# SCH_Senior_Transmitter_2026-04-06.net
KiCad netlist of a schematic drawn in EasyEDA
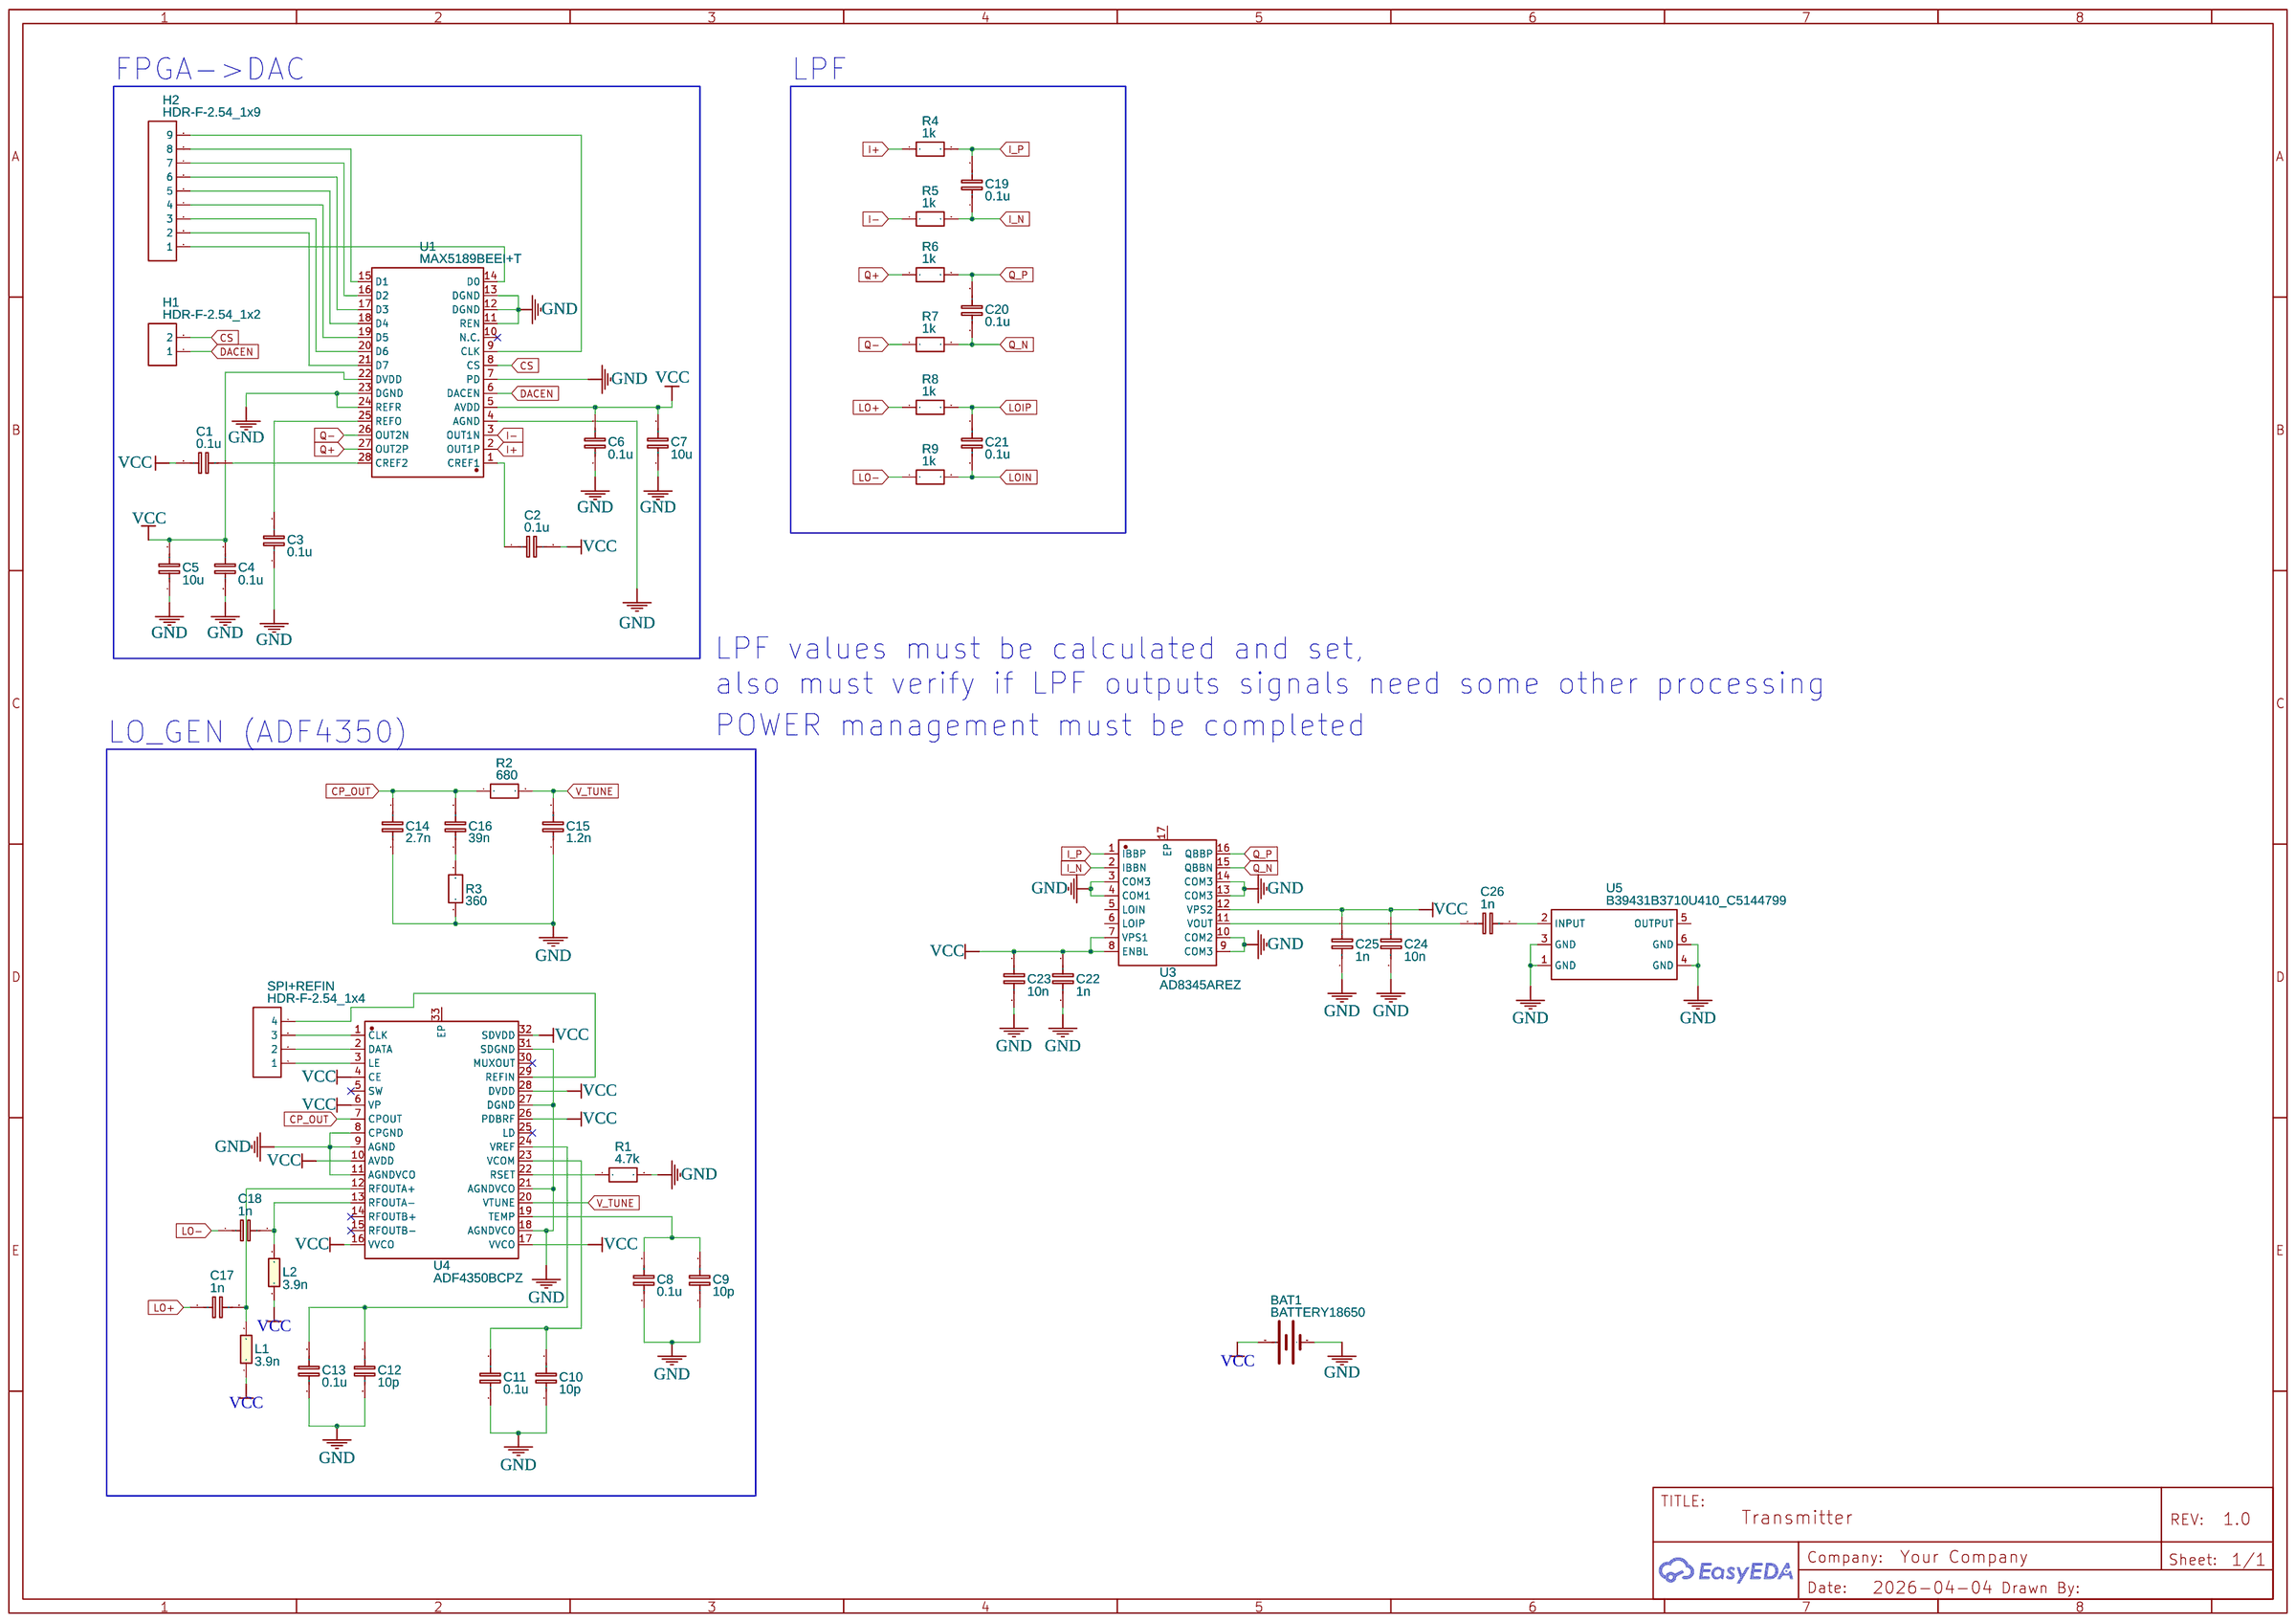
[diagram p0: schematic sheet]

(export (version "E")
  (design (tool "Eeschema 10.0.6"))
  (components
    (comp (ref "BAT1") (value "BATTERY18650") (libsource (lib "") (part "BATTERY18650")))
    (comp (ref "C1") (value "0.1u") (libsource (lib "") (part "C_0603_EU_3")))
    (comp (ref "C2") (value "0.1u") (libsource (lib "") (part "C_0603_EU_3")))
    (comp (ref "C3") (value "0.1u") (libsource (lib "") (part "C_0603_EU_1")))
    (comp (ref "C4") (value "0.1u") (libsource (lib "") (part "C_0603_EU_1")))
    (comp (ref "C5") (value "10u") (libsource (lib "") (part "C_0603_EU_1")))
    (comp (ref "C6") (value "0.1u") (libsource (lib "") (part "C_0603_EU_4")))
    (comp (ref "C7") (value "10u") (libsource (lib "") (part "C_0603_EU_4")))
    (comp (ref "C8") (value "0.1u") (libsource (lib "") (part "C_0603_EU_5")))
    (comp (ref "C9") (value "10p") (libsource (lib "") (part "C_0603_EU_5")))
    (comp (ref "C10") (value "10p") (libsource (lib "") (part "C_0603_EU_4")))
    (comp (ref "C11") (value "0.1u") (libsource (lib "") (part "C_0603_EU_4")))
    (comp (ref "C12") (value "10p") (libsource (lib "") (part "C_0603_EU_4")))
    (comp (ref "C13") (value "0.1u") (libsource (lib "") (part "C_0603_EU_1")))
    (comp (ref "C14") (value "2.7n") (libsource (lib "") (part "C_0603_EU_5")))
    (comp (ref "C15") (value "1.2n") (libsource (lib "") (part "C_0603_EU_5")))
    (comp (ref "C16") (value "39n") (libsource (lib "") (part "C_0603_EU_5")))
    (comp (ref "C17") (value "1n") (libsource (lib "") (part "C_0603_EU_3")))
    (comp (ref "C18") (value "1n") (libsource (lib "") (part "C_0603_EU_6")))
    (comp (ref "C19") (value "0.1u") (libsource (lib "") (part "C_0603_EU_1")))
    (comp (ref "C20") (value "0.1u") (libsource (lib "") (part "C_0603_EU_1")))
    (comp (ref "C21") (value "0.1u") (libsource (lib "") (part "C_0603_EU_1")))
    (comp (ref "C22") (value "1n") (libsource (lib "") (part "C_0603_EU")))
    (comp (ref "C23") (value "10n") (libsource (lib "") (part "C_0603_EU")))
    (comp (ref "C24") (value "10n") (libsource (lib "") (part "C_0603_EU")))
    (comp (ref "C25") (value "1n") (libsource (lib "") (part "C_0603_EU")))
    (comp (ref "C26") (value "1n") (libsource (lib "") (part "C_0603_EU_2")))
    (comp (ref "H1") (value "HDR-F-2.54_1x2") (libsource (lib "") (part "HDR-F-2.54_1x2")))
    (comp (ref "H2") (value "HDR-F-2.54_1x9") (libsource (lib "") (part "HDR-F-2.54_1x9")))
    (comp (ref "L1") (value "3.9n") (libsource (lib "") (part "L0603_EU")))
    (comp (ref "L2") (value "3.9n") (libsource (lib "") (part "L0603_EU")))
    (comp (ref "R1") (value "4.7k") (libsource (lib "") (part "R_0603_EU")))
    (comp (ref "R2") (value "680") (libsource (lib "") (part "R_0603_EU")))
    (comp (ref "R3") (value "360") (libsource (lib "") (part "R_0603_EU_1")))
    (comp (ref "R4") (value "1k") (libsource (lib "") (part "R_0603_EU")))
    (comp (ref "R5") (value "1k") (libsource (lib "") (part "R_0603_EU")))
    (comp (ref "R6") (value "1k") (libsource (lib "") (part "R_0603_EU")))
    (comp (ref "R7") (value "1k") (libsource (lib "") (part "R_0603_EU")))
    (comp (ref "R8") (value "1k") (libsource (lib "") (part "R_0603_EU")))
    (comp (ref "R9") (value "1k") (libsource (lib "") (part "R_0603_EU")))
    (comp (ref "SPI+REFIN") (value "HDR-F-2.54_1x4") (libsource (lib "") (part "HDR-F-2.54_1x4")))
    (comp (ref "U1")
      (value "MAX5189BEEI+T")
      (fields (field (name "Manufacturer") "ADI(亚德诺)/MAXIM(美信)"))
      (libsource (lib "") (part "MAX5189BEEI+T"))
    )
    (comp (ref "U3")
      (value "AD8345AREZ")
      (fields (field (name "Manufacturer") "ADI(亚德诺)"))
      (libsource (lib "") (part "AD8345AREZ"))
    )
    (comp (ref "U4")
      (value "ADF4350BCPZ")
      (fields (field (name "Manufacturer") "ADI(亚德诺)"))
      (libsource (lib "") (part "ADF4350BCPZ"))
    )
    (comp (ref "U5")
      (value "B39431B3710U410_C5144799")
      (fields (field (name "Manufacturer Part") "B39431B3710U410"))
      (libsource (lib "") (part "B39431B3710U410_C5144799"))
    )
  )
  (nets
    (net (code "1") (name "CP_OUT") (class "Default")
      (node (ref "C14") (pin "2") (pinfunction "2_2") (pintype "unspecified"))
      (node (ref "C16") (pin "2") (pinfunction "2_2") (pintype "unspecified"))
      (node (ref "R2") (pin "1") (pinfunction "1_1") (pintype "unspecified"))
      (node (ref "U4") (pin "7") (pinfunction "CPOUT_7") (pintype "unspecified"))
    )
    (net (code "2") (name "CS") (class "Default")
      (node (ref "H1") (pin "2") (pinfunction "2_2") (pintype "input"))
      (node (ref "U1") (pin "8") (pinfunction "CS_8") (pintype "unspecified"))
    )
    (net (code "3") (name "DACEN") (class "Default")
      (node (ref "H1") (pin "1") (pinfunction "1_1") (pintype "input"))
      (node (ref "U1") (pin "6") (pinfunction "DACEN_6") (pintype "unspecified"))
    )
    (net (code "4") (name "GND") (class "Default")
      (node (ref "BAT1") (pin "GND@1") (pinfunction "-_GND@1") (pintype "passive"))
      (node (ref "C10") (pin "1") (pinfunction "1_1") (pintype "unspecified"))
      (node (ref "C11") (pin "1") (pinfunction "1_1") (pintype "unspecified"))
      (node (ref "C12") (pin "1") (pinfunction "1_1") (pintype "unspecified"))
      (node (ref "C13") (pin "1") (pinfunction "1_1") (pintype "unspecified"))
      (node (ref "C14") (pin "1") (pinfunction "1_1") (pintype "unspecified"))
      (node (ref "C15") (pin "1") (pinfunction "1_1") (pintype "unspecified"))
      (node (ref "C22") (pin "2") (pinfunction "2_2") (pintype "unspecified"))
      (node (ref "C23") (pin "2") (pinfunction "2_2") (pintype "unspecified"))
      (node (ref "C24") (pin "2") (pinfunction "2_2") (pintype "unspecified"))
      (node (ref "C25") (pin "2") (pinfunction "2_2") (pintype "unspecified"))
      (node (ref "C3") (pin "1") (pinfunction "1_1") (pintype "unspecified"))
      (node (ref "C4") (pin "1") (pinfunction "1_1") (pintype "unspecified"))
      (node (ref "C5") (pin "1") (pinfunction "1_1") (pintype "unspecified"))
      (node (ref "C6") (pin "1") (pinfunction "1_1") (pintype "unspecified"))
      (node (ref "C7") (pin "1") (pinfunction "1_1") (pintype "unspecified"))
      (node (ref "C8") (pin "1") (pinfunction "1_1") (pintype "unspecified"))
      (node (ref "C9") (pin "1") (pinfunction "1_1") (pintype "unspecified"))
      (node (ref "R1") (pin "2") (pinfunction "2_2") (pintype "unspecified"))
      (node (ref "R3") (pin "1") (pinfunction "1_1") (pintype "unspecified"))
      (node (ref "U1") (pin "11") (pinfunction "REN_11") (pintype "unspecified"))
      (node (ref "U1") (pin "12") (pinfunction "DGND_12") (pintype "unspecified"))
      (node (ref "U1") (pin "13") (pinfunction "DGND_13") (pintype "unspecified"))
      (node (ref "U1") (pin "23") (pinfunction "DGND_23") (pintype "unspecified"))
      (node (ref "U1") (pin "24") (pinfunction "REFR_24") (pintype "unspecified"))
      (node (ref "U1") (pin "4") (pinfunction "AGND_4") (pintype "unspecified"))
      (node (ref "U1") (pin "7") (pinfunction "PD_7") (pintype "unspecified"))
      (node (ref "U3") (pin "10") (pinfunction "COM2_10") (pintype "unspecified"))
      (node (ref "U3") (pin "13") (pinfunction "COM3_13") (pintype "unspecified"))
      (node (ref "U3") (pin "14") (pinfunction "COM3_14") (pintype "unspecified"))
      (node (ref "U3") (pin "3") (pinfunction "COM3_3") (pintype "unspecified"))
      (node (ref "U3") (pin "4") (pinfunction "COM1_4") (pintype "unspecified"))
      (node (ref "U3") (pin "9") (pinfunction "COM3_9") (pintype "unspecified"))
      (node (ref "U4") (pin "11") (pinfunction "AGNDVCO_11") (pintype "unspecified"))
      (node (ref "U4") (pin "18") (pinfunction "AGNDVCO_18") (pintype "unspecified"))
      (node (ref "U4") (pin "21") (pinfunction "AGNDVCO_21") (pintype "unspecified"))
      (node (ref "U4") (pin "27") (pinfunction "DGND_27") (pintype "unspecified"))
      (node (ref "U4") (pin "31") (pinfunction "SDGND_31") (pintype "unspecified"))
      (node (ref "U4") (pin "8") (pinfunction "CPGND_8") (pintype "unspecified"))
      (node (ref "U4") (pin "9") (pinfunction "AGND_9") (pintype "unspecified"))
      (node (ref "U5") (pin "1") (pinfunction "GND_1") (pintype "unspecified"))
      (node (ref "U5") (pin "3") (pinfunction "GND_3") (pintype "unspecified"))
      (node (ref "U5") (pin "4") (pinfunction "GND_4") (pintype "unspecified"))
      (node (ref "U5") (pin "6") (pinfunction "GND_6") (pintype "unspecified"))
    )
    (net (code "5") (name "I+") (class "Default")
      (node (ref "R4") (pin "1") (pinfunction "1_1") (pintype "unspecified"))
      (node (ref "U1") (pin "2") (pinfunction "OUT1P_2") (pintype "unspecified"))
    )
    (net (code "6") (name "I-") (class "Default")
      (node (ref "R5") (pin "1") (pinfunction "1_1") (pintype "unspecified"))
      (node (ref "U1") (pin "3") (pinfunction "OUT1N_3") (pintype "unspecified"))
    )
    (net (code "7") (name "I_N") (class "Default")
      (node (ref "C19") (pin "1") (pinfunction "1_1") (pintype "unspecified"))
      (node (ref "R5") (pin "2") (pinfunction "2_2") (pintype "unspecified"))
      (node (ref "U3") (pin "2") (pinfunction "IBBN_2") (pintype "unspecified"))
    )
    (net (code "8") (name "I_P") (class "Default")
      (node (ref "C19") (pin "2") (pinfunction "2_2") (pintype "unspecified"))
      (node (ref "R4") (pin "2") (pinfunction "2_2") (pintype "unspecified"))
      (node (ref "U3") (pin "1") (pinfunction "IBBP_1") (pintype "unspecified"))
    )
    (net (code "9") (name "LO+") (class "Default")
      (node (ref "C17") (pin "1") (pinfunction "1_1") (pintype "unspecified"))
      (node (ref "R8") (pin "1") (pinfunction "1_1") (pintype "unspecified"))
    )
    (net (code "10") (name "LO-") (class "Default")
      (node (ref "C18") (pin "1") (pinfunction "1_1") (pintype "unspecified"))
      (node (ref "R9") (pin "1") (pinfunction "1_1") (pintype "unspecified"))
    )
    (net (code "11") (name "LOIN") (class "Default")
      (node (ref "C21") (pin "1") (pinfunction "1_1") (pintype "unspecified"))
      (node (ref "R9") (pin "2") (pinfunction "2_2") (pintype "unspecified"))
    )
    (net (code "12") (name "LOIP") (class "Default")
      (node (ref "C21") (pin "2") (pinfunction "2_2") (pintype "unspecified"))
      (node (ref "R8") (pin "2") (pinfunction "2_2") (pintype "unspecified"))
    )
    (net (code "13") (name "Net-(C16-Pad1)") (class "Default")
      (node (ref "C16") (pin "1") (pinfunction "1_1") (pintype "unspecified"))
      (node (ref "R3") (pin "2") (pinfunction "2_2") (pintype "unspecified"))
    )
    (net (code "14") (name "Net-(U1-CLK)") (class "Default")
      (node (ref "H2") (pin "9") (pinfunction "9_9") (pintype "unspecified"))
      (node (ref "U1") (pin "9") (pinfunction "CLK_9") (pintype "unspecified"))
    )
    (net (code "15") (name "Net-(U1-CREF1)") (class "Default")
      (node (ref "C2") (pin "1") (pinfunction "1_1") (pintype "unspecified"))
      (node (ref "U1") (pin "1") (pinfunction "CREF1_1") (pintype "unspecified"))
    )
    (net (code "16") (name "Net-(U1-CREF2)") (class "Default")
      (node (ref "C1") (pin "2") (pinfunction "2_2") (pintype "unspecified"))
      (node (ref "U1") (pin "28") (pinfunction "CREF2_28") (pintype "unspecified"))
    )
    (net (code "17") (name "Net-(U1-D0)") (class "Default")
      (node (ref "H2") (pin "1") (pinfunction "1_1") (pintype "unspecified"))
      (node (ref "U1") (pin "14") (pinfunction "D0_14") (pintype "unspecified"))
    )
    (net (code "18") (name "Net-(U1-D1)") (class "Default")
      (node (ref "H2") (pin "8") (pinfunction "8_8") (pintype "unspecified"))
      (node (ref "U1") (pin "15") (pinfunction "D1_15") (pintype "unspecified"))
    )
    (net (code "19") (name "Net-(U1-D2)") (class "Default")
      (node (ref "H2") (pin "7") (pinfunction "7_7") (pintype "unspecified"))
      (node (ref "U1") (pin "16") (pinfunction "D2_16") (pintype "unspecified"))
    )
    (net (code "20") (name "Net-(U1-D3)") (class "Default")
      (node (ref "H2") (pin "6") (pinfunction "6_6") (pintype "unspecified"))
      (node (ref "U1") (pin "17") (pinfunction "D3_17") (pintype "unspecified"))
    )
    (net (code "21") (name "Net-(U1-D4)") (class "Default")
      (node (ref "H2") (pin "5") (pinfunction "5_5") (pintype "unspecified"))
      (node (ref "U1") (pin "18") (pinfunction "D4_18") (pintype "unspecified"))
    )
    (net (code "22") (name "Net-(U1-D5)") (class "Default")
      (node (ref "H2") (pin "4") (pinfunction "4_4") (pintype "unspecified"))
      (node (ref "U1") (pin "19") (pinfunction "D5_19") (pintype "unspecified"))
    )
    (net (code "23") (name "Net-(U1-D6)") (class "Default")
      (node (ref "H2") (pin "3") (pinfunction "3_3") (pintype "unspecified"))
      (node (ref "U1") (pin "20") (pinfunction "D6_20") (pintype "unspecified"))
    )
    (net (code "24") (name "Net-(U1-D7)") (class "Default")
      (node (ref "H2") (pin "2") (pinfunction "2_2") (pintype "unspecified"))
      (node (ref "U1") (pin "21") (pinfunction "D7_21") (pintype "unspecified"))
    )
    (net (code "25") (name "Net-(U1-REFO)") (class "Default")
      (node (ref "C3") (pin "2") (pinfunction "2_2") (pintype "unspecified"))
      (node (ref "U1") (pin "25") (pinfunction "REFO_25") (pintype "unspecified"))
    )
    (net (code "26") (name "Net-(U3-VOUT)") (class "Default")
      (node (ref "C26") (pin "1") (pinfunction "1_1") (pintype "unspecified"))
      (node (ref "U3") (pin "11") (pinfunction "VOUT_11") (pintype "unspecified"))
    )
    (net (code "27") (name "Net-(U4-CLK)") (class "Default")
      (node (ref "SPI+REFIN") (pin "3") (pinfunction "3_3") (pintype "unspecified"))
      (node (ref "U4") (pin "1") (pinfunction "CLK_1") (pintype "unspecified"))
    )
    (net (code "28") (name "Net-(U4-DATA)") (class "Default")
      (node (ref "SPI+REFIN") (pin "2") (pinfunction "2_2") (pintype "unspecified"))
      (node (ref "U4") (pin "2") (pinfunction "DATA_2") (pintype "unspecified"))
    )
    (net (code "29") (name "Net-(U4-LE)") (class "Default")
      (node (ref "SPI+REFIN") (pin "1") (pinfunction "1_1") (pintype "unspecified"))
      (node (ref "U4") (pin "3") (pinfunction "LE_3") (pintype "unspecified"))
    )
    (net (code "30") (name "Net-(U4-REFIN)") (class "Default")
      (node (ref "SPI+REFIN") (pin "4") (pinfunction "4_4") (pintype "unspecified"))
      (node (ref "U4") (pin "29") (pinfunction "REFIN_29") (pintype "unspecified"))
    )
    (net (code "31") (name "Net-(U4-RFOUTA+)") (class "Default")
      (node (ref "C17") (pin "2") (pinfunction "2_2") (pintype "unspecified"))
      (node (ref "L1") (pin "2") (pinfunction "2_2") (pintype "unspecified"))
      (node (ref "U4") (pin "12") (pinfunction "RFOUTA+_12") (pintype "unspecified"))
    )
    (net (code "32") (name "Net-(U4-RFOUTA-)") (class "Default")
      (node (ref "C18") (pin "2") (pinfunction "2_2") (pintype "unspecified"))
      (node (ref "L2") (pin "2") (pinfunction "2_2") (pintype "unspecified"))
      (node (ref "U4") (pin "13") (pinfunction "RFOUTA-_13") (pintype "unspecified"))
    )
    (net (code "33") (name "Net-(U4-RSET)") (class "Default")
      (node (ref "R1") (pin "1") (pinfunction "1_1") (pintype "unspecified"))
      (node (ref "U4") (pin "22") (pinfunction "RSET_22") (pintype "unspecified"))
    )
    (net (code "34") (name "Net-(U4-TEMP)") (class "Default")
      (node (ref "C8") (pin "2") (pinfunction "2_2") (pintype "unspecified"))
      (node (ref "C9") (pin "2") (pinfunction "2_2") (pintype "unspecified"))
      (node (ref "U4") (pin "19") (pinfunction "TEMP_19") (pintype "unspecified"))
    )
    (net (code "35") (name "Net-(U4-VCOM)") (class "Default")
      (node (ref "C10") (pin "2") (pinfunction "2_2") (pintype "unspecified"))
      (node (ref "C11") (pin "2") (pinfunction "2_2") (pintype "unspecified"))
      (node (ref "U4") (pin "23") (pinfunction "VCOM_23") (pintype "unspecified"))
    )
    (net (code "36") (name "Net-(U4-VREF)") (class "Default")
      (node (ref "C12") (pin "2") (pinfunction "2_2") (pintype "unspecified"))
      (node (ref "C13") (pin "2") (pinfunction "2_2") (pintype "unspecified"))
      (node (ref "U4") (pin "24") (pinfunction "VREF_24") (pintype "unspecified"))
    )
    (net (code "37") (name "Net-(U5-INPUT)") (class "Default")
      (node (ref "C26") (pin "2") (pinfunction "2_2") (pintype "unspecified"))
      (node (ref "U5") (pin "2") (pinfunction "INPUT_2") (pintype "unspecified"))
    )
    (net (code "38") (name "Q+") (class "Default")
      (node (ref "R6") (pin "1") (pinfunction "1_1") (pintype "unspecified"))
      (node (ref "U1") (pin "27") (pinfunction "OUT2P_27") (pintype "unspecified"))
    )
    (net (code "39") (name "Q-") (class "Default")
      (node (ref "R7") (pin "1") (pinfunction "1_1") (pintype "unspecified"))
      (node (ref "U1") (pin "26") (pinfunction "OUT2N_26") (pintype "unspecified"))
    )
    (net (code "40") (name "Q_N") (class "Default")
      (node (ref "C20") (pin "1") (pinfunction "1_1") (pintype "unspecified"))
      (node (ref "R7") (pin "2") (pinfunction "2_2") (pintype "unspecified"))
      (node (ref "U3") (pin "15") (pinfunction "QBBN_15") (pintype "unspecified"))
    )
    (net (code "41") (name "Q_P") (class "Default")
      (node (ref "C20") (pin "2") (pinfunction "2_2") (pintype "unspecified"))
      (node (ref "R6") (pin "2") (pinfunction "2_2") (pintype "unspecified"))
      (node (ref "U3") (pin "16") (pinfunction "QBBP_16") (pintype "unspecified"))
    )
    (net (code "42") (name "VCC") (class "Default")
      (node (ref "BAT1") (pin "PWR@1") (pinfunction "+_PWR@1") (pintype "passive"))
      (node (ref "C1") (pin "1") (pinfunction "1_1") (pintype "unspecified"))
      (node (ref "C2") (pin "2") (pinfunction "2_2") (pintype "unspecified"))
      (node (ref "C22") (pin "1") (pinfunction "1_1") (pintype "unspecified"))
      (node (ref "C23") (pin "1") (pinfunction "1_1") (pintype "unspecified"))
      (node (ref "C24") (pin "1") (pinfunction "1_1") (pintype "unspecified"))
      (node (ref "C25") (pin "1") (pinfunction "1_1") (pintype "unspecified"))
      (node (ref "C4") (pin "2") (pinfunction "2_2") (pintype "unspecified"))
      (node (ref "C5") (pin "2") (pinfunction "2_2") (pintype "unspecified"))
      (node (ref "C6") (pin "2") (pinfunction "2_2") (pintype "unspecified"))
      (node (ref "C7") (pin "2") (pinfunction "2_2") (pintype "unspecified"))
      (node (ref "L1") (pin "1") (pinfunction "1_1") (pintype "unspecified"))
      (node (ref "L2") (pin "1") (pinfunction "1_1") (pintype "unspecified"))
      (node (ref "U1") (pin "22") (pinfunction "DVDD_22") (pintype "unspecified"))
      (node (ref "U1") (pin "5") (pinfunction "AVDD_5") (pintype "unspecified"))
      (node (ref "U3") (pin "12") (pinfunction "VPS2_12") (pintype "unspecified"))
      (node (ref "U3") (pin "7") (pinfunction "VPS1_7") (pintype "unspecified"))
      (node (ref "U3") (pin "8") (pinfunction "ENBL_8") (pintype "unspecified"))
      (node (ref "U4") (pin "10") (pinfunction "AVDD_10") (pintype "unspecified"))
      (node (ref "U4") (pin "16") (pinfunction "VVCO_16") (pintype "unspecified"))
      (node (ref "U4") (pin "17") (pinfunction "VVCO_17") (pintype "unspecified"))
      (node (ref "U4") (pin "26") (pinfunction "PDBRF_26") (pintype "unspecified"))
      (node (ref "U4") (pin "28") (pinfunction "DVDD_28") (pintype "unspecified"))
      (node (ref "U4") (pin "32") (pinfunction "SDVDD_32") (pintype "unspecified"))
      (node (ref "U4") (pin "4") (pinfunction "CE_4") (pintype "unspecified"))
      (node (ref "U4") (pin "6") (pinfunction "VP_6") (pintype "unspecified"))
    )
    (net (code "43") (name "V_TUNE") (class "Default")
      (node (ref "C15") (pin "2") (pinfunction "2_2") (pintype "unspecified"))
      (node (ref "R2") (pin "2") (pinfunction "2_2") (pintype "unspecified"))
      (node (ref "U4") (pin "20") (pinfunction "VTUNE_20") (pintype "unspecified"))
    )
    (net (code "44") (name "unconnected-(U1-N.C.-Pad10)") (class "Default")
      (node (ref "U1") (pin "10") (pinfunction "N.C._10") (pintype "unspecified+no_connect"))
    )
    (net (code "45") (name "unconnected-(U3-EP-Pad17)") (class "Default")
      (node (ref "U3") (pin "17") (pinfunction "EP_17") (pintype "unspecified"))
    )
    (net (code "46") (name "unconnected-(U3-LOIN-Pad5)") (class "Default")
      (node (ref "U3") (pin "5") (pinfunction "LOIN_5") (pintype "unspecified"))
    )
    (net (code "47") (name "unconnected-(U3-LOIP-Pad6)") (class "Default")
      (node (ref "U3") (pin "6") (pinfunction "LOIP_6") (pintype "unspecified"))
    )
    (net (code "48") (name "unconnected-(U4-EP-Pad33)") (class "Default")
      (node (ref "U4") (pin "33") (pinfunction "EP_33") (pintype "unspecified"))
    )
    (net (code "49") (name "unconnected-(U4-LD-Pad25)") (class "Default")
      (node (ref "U4") (pin "25") (pinfunction "LD_25") (pintype "unspecified+no_connect"))
    )
    (net (code "50") (name "unconnected-(U4-MUXOUT-Pad30)") (class "Default")
      (node (ref "U4") (pin "30") (pinfunction "MUXOUT_30") (pintype "unspecified+no_connect"))
    )
    (net (code "51") (name "unconnected-(U4-RFOUTB+-Pad14)") (class "Default")
      (node (ref "U4") (pin "14") (pinfunction "RFOUTB+_14") (pintype "unspecified+no_connect"))
    )
    (net (code "52") (name "unconnected-(U4-RFOUTB--Pad15)") (class "Default")
      (node (ref "U4") (pin "15") (pinfunction "RFOUTB-_15") (pintype "unspecified+no_connect"))
    )
    (net (code "53") (name "unconnected-(U4-SW-Pad5)") (class "Default")
      (node (ref "U4") (pin "5") (pinfunction "SW_5") (pintype "unspecified+no_connect"))
    )
    (net (code "54") (name "unconnected-(U5-OUTPUT-Pad5)") (class "Default")
      (node (ref "U5") (pin "5") (pinfunction "OUTPUT_5") (pintype "unspecified"))
    )
  )
)
